# 3_mcu.net
KiCad netlist of a schematic drawn in Altium Designer
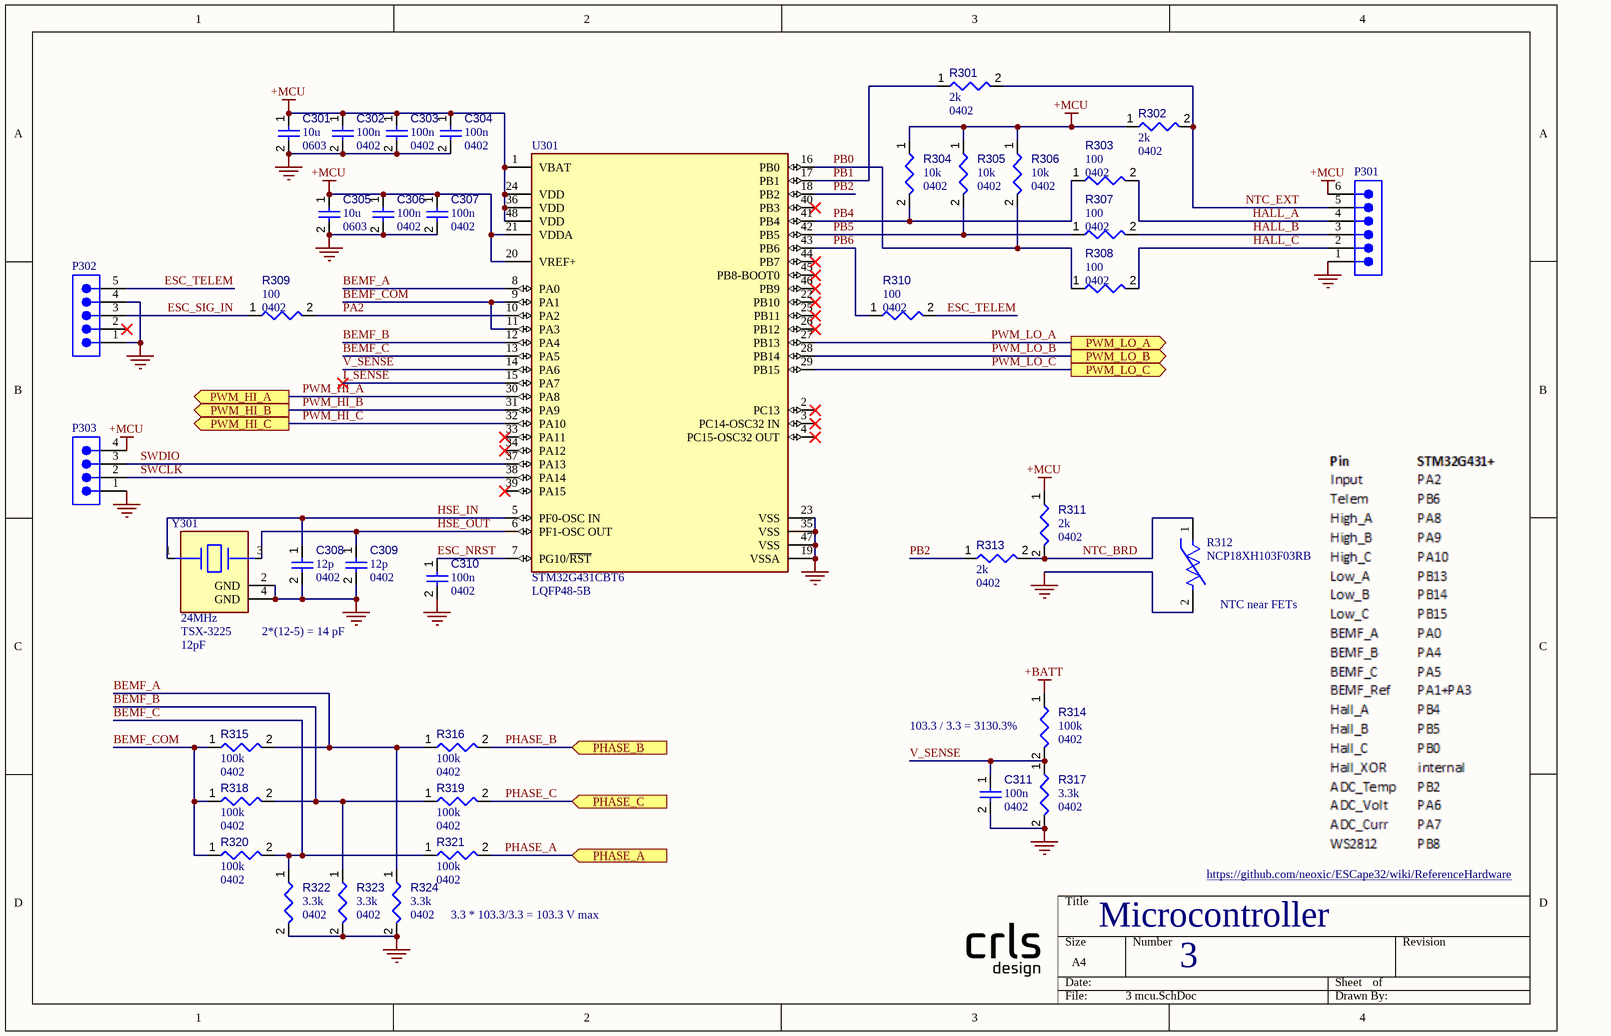
[diagram p0: 3 mcu.SchDoc]

(export (version "E")
  (design (tool "Eeschema 10.0.6"))
  (components
    (comp (ref "C301")
      (value "10u")
      (footprint "CAPC0603(1608)100_L")
      (description "Capacitor")
      (fields
        (field (name "CASE/PACKAGE") "0603")
        (field (name "TOLERANCE") "20%")
        (field (name "Comment") "Capacitors,ceramic,0603,20%,10u,25V")
      )
      (libsource (lib "UBC Uncrewed Aircraft Systems") (part "CAP-NP-2"))
    )
    (comp (ref "C302")
      (value "100n")
      (footprint "CAPC0402(1005)60_L")
      (description "Capacitor")
      (fields
        (field (name "CASE/PACKAGE") "0402")
        (field (name "TOLERANCE") "20%")
        (field (name "Comment") "Capacitors,ceramic,0402,20%,100n,16V")
      )
      (libsource (lib "UBC Uncrewed Aircraft Systems") (part "CAP-NP-2"))
    )
    (comp (ref "C303")
      (value "100n")
      (footprint "CAPC0402(1005)60_L")
      (description "Capacitor")
      (fields
        (field (name "CASE/PACKAGE") "0402")
        (field (name "TOLERANCE") "20%")
        (field (name "Comment") "Capacitors,ceramic,0402,20%,100n,16V")
      )
      (libsource (lib "UBC Uncrewed Aircraft Systems") (part "CAP-NP-2"))
    )
    (comp (ref "C304")
      (value "100n")
      (footprint "CAPC0402(1005)60_L")
      (description "Capacitor")
      (fields
        (field (name "CASE/PACKAGE") "0402")
        (field (name "TOLERANCE") "20%")
        (field (name "Comment") "Capacitors,ceramic,0402,20%,100n,16V")
      )
      (libsource (lib "UBC Uncrewed Aircraft Systems") (part "CAP-NP-2"))
    )
    (comp (ref "C305")
      (value "10u")
      (footprint "CAPC0603(1608)100_L")
      (description "Capacitor")
      (fields
        (field (name "CASE/PACKAGE") "0603")
        (field (name "TOLERANCE") "20%")
        (field (name "Comment") "Capacitors,ceramic,0603,20%,10u,25V")
      )
      (libsource (lib "UBC Uncrewed Aircraft Systems") (part "CAP-NP-2"))
    )
    (comp (ref "C306")
      (value "100n")
      (footprint "CAPC0402(1005)60_L")
      (description "Capacitor")
      (fields
        (field (name "CASE/PACKAGE") "0402")
        (field (name "TOLERANCE") "20%")
        (field (name "Comment") "Capacitors,ceramic,0402,20%,100n,16V")
      )
      (libsource (lib "UBC Uncrewed Aircraft Systems") (part "CAP-NP-2"))
    )
    (comp (ref "C307")
      (value "100n")
      (footprint "CAPC0402(1005)60_L")
      (description "Capacitor")
      (fields
        (field (name "CASE/PACKAGE") "0402")
        (field (name "TOLERANCE") "20%")
        (field (name "Comment") "Capacitors,ceramic,0402,20%,100n,16V")
      )
      (libsource (lib "UBC Uncrewed Aircraft Systems") (part "CAP-NP-2"))
    )
    (comp (ref "C308")
      (value "12p")
      (footprint "CAPC0402(1005)60_L")
      (description "Capacitor")
      (fields
        (field (name "CASE/PACKAGE") "0402")
        (field (name "TOLERANCE") "10%")
        (field (name "Comment") "Capacitors,ceramic,0402,10%,12p,50V")
      )
      (libsource (lib "UBC Uncrewed Aircraft Systems") (part "CAP-NP-2"))
    )
    (comp (ref "C309")
      (value "12p")
      (footprint "CAPC0402(1005)60_L")
      (description "Capacitor")
      (fields
        (field (name "CASE/PACKAGE") "0402")
        (field (name "TOLERANCE") "10%")
        (field (name "Comment") "Capacitors,ceramic,0402,10%,12p,50V")
      )
      (libsource (lib "UBC Uncrewed Aircraft Systems") (part "CAP-NP-2"))
    )
    (comp (ref "C310")
      (value "100n")
      (footprint "CAPC0402(1005)60_L")
      (description "Capacitor")
      (fields
        (field (name "CASE/PACKAGE") "0402")
        (field (name "TOLERANCE") "20%")
        (field (name "Comment") "Capacitors,ceramic,0402,20%,100n,16V")
      )
      (libsource (lib "UBC Uncrewed Aircraft Systems") (part "CAP-NP-2"))
    )
    (comp (ref "C311")
      (value "100n")
      (footprint "CAPC0402(1005)60_L")
      (description "Capacitor")
      (fields
        (field (name "CASE/PACKAGE") "0402")
        (field (name "TOLERANCE") "20%")
        (field (name "Comment") "Capacitors,ceramic,0402,20%,100n,16V")
      )
      (libsource (lib "UBC Uncrewed Aircraft Systems") (part "CAP-NP-2"))
    )
    (comp (ref "P301")
      (value "61300611121")
      (footprint "61300611121")
      (libsource (lib "Altium Content Vault") (part "Header_Male_1R_06P"))
    )
    (comp (ref "P302")
      (value "61300511121")
      (footprint "61300511121")
      (libsource (lib "Altium Content Vault") (part "Header_Male_1R_05P"))
    )
    (comp (ref "P303")
      (value "61300411121")
      (footprint "61300411121")
      (libsource (lib "Altium Content Vault") (part "Header_Male_1R_04P"))
    )
    (comp (ref "R301")
      (value "2k")
      (footprint "RESC0402(1005)_L")
      (description "Resistor")
      (fields
        (field (name "CASE/PACKAGE") "0402")
        (field (name "TOLERANCE") "1%")
        (field (name "Comment") "Resistors,0402,1%,2k")
      )
      (libsource (lib "UBC Uncrewed Aircraft Systems") (part "RES-2"))
    )
    (comp (ref "R302")
      (value "2k")
      (footprint "RESC0402(1005)_L")
      (description "Resistor")
      (fields
        (field (name "CASE/PACKAGE") "0402")
        (field (name "TOLERANCE") "1%")
        (field (name "Comment") "Resistors,0402,1%,2k")
      )
      (libsource (lib "UBC Uncrewed Aircraft Systems") (part "RES-2"))
    )
    (comp (ref "R303")
      (value "100")
      (footprint "RESC0402(1005)_L")
      (description "Resistor")
      (fields
        (field (name "CASE/PACKAGE") "0402")
        (field (name "TOLERANCE") "1%")
        (field (name "Comment") "Resistors,0402,1%,100")
      )
      (libsource (lib "UBC Uncrewed Aircraft Systems") (part "RES-2"))
    )
    (comp (ref "R304")
      (value "10k")
      (footprint "RESC0402(1005)_L")
      (description "Resistor")
      (fields
        (field (name "CASE/PACKAGE") "0402")
        (field (name "TOLERANCE") "1%")
        (field (name "Comment") "Resistors,0402,1%,10k")
      )
      (libsource (lib "UBC Uncrewed Aircraft Systems") (part "RES-2"))
    )
    (comp (ref "R305")
      (value "10k")
      (footprint "RESC0402(1005)_L")
      (description "Resistor")
      (fields
        (field (name "CASE/PACKAGE") "0402")
        (field (name "TOLERANCE") "1%")
        (field (name "Comment") "Resistors,0402,1%,10k")
      )
      (libsource (lib "UBC Uncrewed Aircraft Systems") (part "RES-2"))
    )
    (comp (ref "R306")
      (value "10k")
      (footprint "RESC0402(1005)_L")
      (description "Resistor")
      (fields
        (field (name "CASE/PACKAGE") "0402")
        (field (name "TOLERANCE") "1%")
        (field (name "Comment") "Resistors,0402,1%,10k")
      )
      (libsource (lib "UBC Uncrewed Aircraft Systems") (part "RES-2"))
    )
    (comp (ref "R307")
      (value "100")
      (footprint "RESC0402(1005)_L")
      (description "Resistor")
      (fields
        (field (name "CASE/PACKAGE") "0402")
        (field (name "TOLERANCE") "1%")
        (field (name "Comment") "Resistors,0402,1%,100")
      )
      (libsource (lib "UBC Uncrewed Aircraft Systems") (part "RES-2"))
    )
    (comp (ref "R308")
      (value "100")
      (footprint "RESC0402(1005)_L")
      (description "Resistor")
      (fields
        (field (name "CASE/PACKAGE") "0402")
        (field (name "TOLERANCE") "1%")
        (field (name "Comment") "Resistors,0402,1%,100")
      )
      (libsource (lib "UBC Uncrewed Aircraft Systems") (part "RES-2"))
    )
    (comp (ref "R309")
      (value "100")
      (footprint "RESC0402(1005)_L")
      (description "Resistor")
      (fields
        (field (name "CASE/PACKAGE") "0402")
        (field (name "TOLERANCE") "1%")
        (field (name "Comment") "Resistors,0402,1%,100")
      )
      (libsource (lib "UBC Uncrewed Aircraft Systems") (part "RES-2"))
    )
    (comp (ref "R310")
      (value "100")
      (footprint "RESC0402(1005)_L")
      (description "Resistor")
      (fields
        (field (name "CASE/PACKAGE") "0402")
        (field (name "TOLERANCE") "1%")
        (field (name "Comment") "Resistors,0402,1%,100")
      )
      (libsource (lib "UBC Uncrewed Aircraft Systems") (part "RES-2"))
    )
    (comp (ref "R311")
      (value "2k")
      (footprint "RESC0402(1005)_L")
      (description "Resistor")
      (fields
        (field (name "CASE/PACKAGE") "0402")
        (field (name "TOLERANCE") "1%")
        (field (name "Comment") "Resistors,0402,1%,2k")
      )
      (libsource (lib "UBC Uncrewed Aircraft Systems") (part "RES-2"))
    )
    (comp (ref "R312")
      (value "NCP18XH103F03RB")
      (footprint "FP-NCP18-0_15-MFG")
      (description "NTC Thermistor for Temperature Sensor, 0603, 10kΩ, 1%, 0.1mA, 5V")
      (fields (field (name "TOLERANCE") "1%"))
      (libsource (lib "Altium Content Vault") (part "3b148a6ebabc5fb4d708a66c052d352"))
    )
    (comp (ref "R313")
      (value "2k")
      (footprint "RESC0402(1005)_L")
      (description "Resistor")
      (fields
        (field (name "CASE/PACKAGE") "0402")
        (field (name "TOLERANCE") "1%")
        (field (name "Comment") "Resistors,0402,1%,2k")
      )
      (libsource (lib "UBC Uncrewed Aircraft Systems") (part "RES-2"))
    )
    (comp (ref "R314")
      (value "100k")
      (footprint "RESC0402(1005)_L")
      (description "Resistor")
      (fields
        (field (name "CASE/PACKAGE") "0402")
        (field (name "TOLERANCE") "1%")
        (field (name "Comment") "Resistors,0402,1%,100k")
      )
      (libsource (lib "UBC Uncrewed Aircraft Systems") (part "RES-2"))
    )
    (comp (ref "R315")
      (value "100k")
      (footprint "RESC0402(1005)_L")
      (description "Resistor")
      (fields
        (field (name "CASE/PACKAGE") "0402")
        (field (name "TOLERANCE") "1%")
        (field (name "Comment") "Resistors,0402,1%,100k")
      )
      (libsource (lib "UBC Uncrewed Aircraft Systems") (part "RES-2"))
    )
    (comp (ref "R316")
      (value "100k")
      (footprint "RESC0402(1005)_L")
      (description "Resistor")
      (fields
        (field (name "CASE/PACKAGE") "0402")
        (field (name "TOLERANCE") "1%")
        (field (name "Comment") "Resistors,0402,1%,100k")
      )
      (libsource (lib "UBC Uncrewed Aircraft Systems") (part "RES-2"))
    )
    (comp (ref "R317")
      (value "3.3k")
      (footprint "RESC0402(1005)_L")
      (description "Resistor")
      (fields
        (field (name "CASE/PACKAGE") "0402")
        (field (name "TOLERANCE") "1%")
        (field (name "Comment") "Resistors,0402,1%,3.3k")
      )
      (libsource (lib "UBC Uncrewed Aircraft Systems") (part "RES-2"))
    )
    (comp (ref "R318")
      (value "100k")
      (footprint "RESC0402(1005)_L")
      (description "Resistor")
      (fields
        (field (name "CASE/PACKAGE") "0402")
        (field (name "TOLERANCE") "1%")
        (field (name "Comment") "Resistors,0402,1%,100k")
      )
      (libsource (lib "UBC Uncrewed Aircraft Systems") (part "RES-2"))
    )
    (comp (ref "R319")
      (value "100k")
      (footprint "RESC0402(1005)_L")
      (description "Resistor")
      (fields
        (field (name "CASE/PACKAGE") "0402")
        (field (name "TOLERANCE") "1%")
        (field (name "Comment") "Resistors,0402,1%,100k")
      )
      (libsource (lib "UBC Uncrewed Aircraft Systems") (part "RES-2"))
    )
    (comp (ref "R320")
      (value "100k")
      (footprint "RESC0402(1005)_L")
      (description "Resistor")
      (fields
        (field (name "CASE/PACKAGE") "0402")
        (field (name "TOLERANCE") "1%")
        (field (name "Comment") "Resistors,0402,1%,100k")
      )
      (libsource (lib "UBC Uncrewed Aircraft Systems") (part "RES-2"))
    )
    (comp (ref "R321")
      (value "100k")
      (footprint "RESC0402(1005)_L")
      (description "Resistor")
      (fields
        (field (name "CASE/PACKAGE") "0402")
        (field (name "TOLERANCE") "1%")
        (field (name "Comment") "Resistors,0402,1%,100k")
      )
      (libsource (lib "UBC Uncrewed Aircraft Systems") (part "RES-2"))
    )
    (comp (ref "R322")
      (value "3.3k")
      (footprint "RESC0402(1005)_L")
      (description "Resistor")
      (fields
        (field (name "CASE/PACKAGE") "0402")
        (field (name "TOLERANCE") "1%")
        (field (name "Comment") "Resistors,0402,1%,3.3k")
      )
      (libsource (lib "UBC Uncrewed Aircraft Systems") (part "RES-2"))
    )
    (comp (ref "R323")
      (value "3.3k")
      (footprint "RESC0402(1005)_L")
      (description "Resistor")
      (fields
        (field (name "CASE/PACKAGE") "0402")
        (field (name "TOLERANCE") "1%")
        (field (name "Comment") "Resistors,0402,1%,3.3k")
      )
      (libsource (lib "UBC Uncrewed Aircraft Systems") (part "RES-2"))
    )
    (comp (ref "R324")
      (value "3.3k")
      (footprint "RESC0402(1005)_L")
      (description "Resistor")
      (fields
        (field (name "CASE/PACKAGE") "0402")
        (field (name "TOLERANCE") "1%")
        (field (name "Comment") "Resistors,0402,1%,3.3k")
      )
      (libsource (lib "UBC Uncrewed Aircraft Systems") (part "RES-2"))
    )
    (comp (ref "U301")
      (value "STM32G431CBT6")
      (footprint "FP-LQFP48-5B-MFG")
      (description "MAINSTREAM ARM CORTEX-M4+ MCU 17")
      (fields
        (field (name "MANUFACTURER") "STMicroelectronics")
        (field (name "PACKAGE") "LQFP48-5B")
        (field (name "OCTOPART") "https://octopart.com/stm32g431cbt6-stmicroelectronics-98835224")
      )
      (libsource (lib "Altium Content Vault") (part "08b09c1d51ec08ade740842f2b8671b"))
    )
    (comp (ref "Y301")
      (value "TSX-3225 24.0000MF20G-AC3")
      (footprint "FP-TSX-3225-MFG")
      (description "CRYSTAL 24.0000MHZ 9PF SMD")
      (fields
        (field (name "FREQUENCY") "24MHz")
        (field (name "TOLERANCE") "10ppm")
        (field (name "SERIES") "TSX-3225")
      )
      (libsource (lib "Altium Content Vault") (part "862d5228ea4a4c8f16e8fb874e464c7"))
    )
  )
  (nets
    (net (code "1") (name "+BATT") (class "Default")
      (node (ref "R314") (pin "1") (pinfunction "1_1") (pintype "passive"))
    )
    (net (code "2") (name "+MCU") (class "Default")
      (node (ref "C301") (pin "1") (pinfunction "1_1") (pintype "passive"))
      (node (ref "C302") (pin "1") (pinfunction "1_1") (pintype "passive"))
      (node (ref "C303") (pin "1") (pinfunction "1_1") (pintype "passive"))
      (node (ref "C304") (pin "1") (pinfunction "1_1") (pintype "passive"))
      (node (ref "C305") (pin "1") (pinfunction "1_1") (pintype "passive"))
      (node (ref "C306") (pin "1") (pinfunction "1_1") (pintype "passive"))
      (node (ref "C307") (pin "1") (pinfunction "1_1") (pintype "passive"))
      (node (ref "P301") (pin "6") (pinfunction "6_6") (pintype "passive"))
      (node (ref "P303") (pin "4") (pinfunction "4_4") (pintype "passive"))
      (node (ref "R302") (pin "1") (pinfunction "1_1") (pintype "passive"))
      (node (ref "R304") (pin "1") (pinfunction "1_1") (pintype "passive"))
      (node (ref "R305") (pin "1") (pinfunction "1_1") (pintype "passive"))
      (node (ref "R306") (pin "1") (pinfunction "1_1") (pintype "passive"))
      (node (ref "R311") (pin "1") (pinfunction "1_1") (pintype "passive"))
      (node (ref "U301") (pin "1") (pinfunction "VBAT_1") (pintype "power_in"))
      (node (ref "U301") (pin "20") (pinfunction "VREF+_20") (pintype "power_in"))
      (node (ref "U301") (pin "21") (pinfunction "VDDA_21") (pintype "power_in"))
      (node (ref "U301") (pin "24") (pinfunction "VDD_24") (pintype "power_in"))
      (node (ref "U301") (pin "36") (pinfunction "VDD_36") (pintype "power_in"))
      (node (ref "U301") (pin "48") (pinfunction "VDD_48") (pintype "power_in"))
    )
    (net (code "3") (name "/BEMF_A") (class "Default")
      (node (ref "R315") (pin "2") (pinfunction "2_2") (pintype "passive"))
      (node (ref "R316") (pin "1") (pinfunction "1_1") (pintype "passive"))
      (node (ref "R324") (pin "1") (pinfunction "1_1") (pintype "passive"))
      (node (ref "U301") (pin "8") (pinfunction "PA0_8") (pintype "bidirectional"))
    )
    (net (code "4") (name "/BEMF_B") (class "Default")
      (node (ref "R318") (pin "2") (pinfunction "2_2") (pintype "passive"))
      (node (ref "R319") (pin "1") (pinfunction "1_1") (pintype "passive"))
      (node (ref "R323") (pin "1") (pinfunction "1_1") (pintype "passive"))
      (node (ref "U301") (pin "12") (pinfunction "PA4_12") (pintype "bidirectional"))
    )
    (net (code "5") (name "/BEMF_C") (class "Default")
      (node (ref "R320") (pin "2") (pinfunction "2_2") (pintype "passive"))
      (node (ref "R321") (pin "1") (pinfunction "1_1") (pintype "passive"))
      (node (ref "R322") (pin "1") (pinfunction "1_1") (pintype "passive"))
      (node (ref "U301") (pin "13") (pinfunction "PA5_13") (pintype "bidirectional"))
    )
    (net (code "6") (name "/BEMF_COM") (class "Default")
      (node (ref "R315") (pin "1") (pinfunction "1_1") (pintype "passive"))
      (node (ref "R318") (pin "1") (pinfunction "1_1") (pintype "passive"))
      (node (ref "R320") (pin "1") (pinfunction "1_1") (pintype "passive"))
      (node (ref "U301") (pin "11") (pinfunction "PA3_11") (pintype "bidirectional"))
      (node (ref "U301") (pin "9") (pinfunction "PA1_9") (pintype "bidirectional"))
    )
    (net (code "7") (name "/ESC_NRST") (class "Default")
      (node (ref "C310") (pin "1") (pinfunction "1_1") (pintype "passive"))
      (node (ref "U301") (pin "7") (pinfunction "PG10/~{RST}_7") (pintype "bidirectional"))
    )
    (net (code "8") (name "/ESC_SIG_IN") (class "Default")
      (node (ref "P302") (pin "3") (pinfunction "3_3") (pintype "passive"))
      (node (ref "R309") (pin "1") (pinfunction "1_1") (pintype "passive"))
    )
    (net (code "9") (name "/ESC_TELEM") (class "Default")
      (node (ref "P302") (pin "5") (pinfunction "5_5") (pintype "passive"))
      (node (ref "R310") (pin "2") (pinfunction "2_2") (pintype "passive"))
    )
    (net (code "10") (name "/HALL_A") (class "Default")
      (node (ref "P301") (pin "4") (pinfunction "4_4") (pintype "passive"))
      (node (ref "R303") (pin "2") (pinfunction "2_2") (pintype "passive"))
    )
    (net (code "11") (name "/HALL_B") (class "Default")
      (node (ref "P301") (pin "3") (pinfunction "3_3") (pintype "passive"))
      (node (ref "R307") (pin "2") (pinfunction "2_2") (pintype "passive"))
    )
    (net (code "12") (name "/HALL_C") (class "Default")
      (node (ref "P301") (pin "2") (pinfunction "2_2") (pintype "passive"))
      (node (ref "R308") (pin "2") (pinfunction "2_2") (pintype "passive"))
    )
    (net (code "13") (name "/HSE_IN") (class "Default")
      (node (ref "C308") (pin "1") (pinfunction "1_1") (pintype "passive"))
      (node (ref "U301") (pin "5") (pinfunction "PF0-OSC_IN_5") (pintype "bidirectional"))
      (node (ref "Y301") (pin "1") (pinfunction "1_1") (pintype "passive"))
    )
    (net (code "14") (name "/HSE_OUT") (class "Default")
      (node (ref "C309") (pin "1") (pinfunction "1_1") (pintype "passive"))
      (node (ref "U301") (pin "6") (pinfunction "PF1-OSC_OUT_6") (pintype "bidirectional"))
      (node (ref "Y301") (pin "3") (pinfunction "3_3") (pintype "passive"))
    )
    (net (code "15") (name "/I_SENSE") (class "Default")
      (node (ref "U301") (pin "15") (pinfunction "PA7_15") (pintype "bidirectional+no_connect"))
    )
    (net (code "16") (name "/NTC_BRD") (class "Default")
      (node (ref "R311") (pin "2") (pinfunction "2_2") (pintype "passive"))
      (node (ref "R312") (pin "1") (pinfunction "1_1") (pintype "passive"))
      (node (ref "R313") (pin "2") (pinfunction "2_2") (pintype "passive"))
    )
    (net (code "17") (name "/NTC_EXT") (class "Default")
      (node (ref "P301") (pin "5") (pinfunction "5_5") (pintype "passive"))
      (node (ref "R301") (pin "2") (pinfunction "2_2") (pintype "passive"))
      (node (ref "R302") (pin "2") (pinfunction "2_2") (pintype "passive"))
    )
    (net (code "18") (name "/PA2") (class "Default")
      (node (ref "R309") (pin "2") (pinfunction "2_2") (pintype "passive"))
      (node (ref "U301") (pin "10") (pinfunction "PA2_10") (pintype "bidirectional"))
    )
    (net (code "19") (name "/PB0") (class "Default")
      (node (ref "R306") (pin "2") (pinfunction "2_2") (pintype "passive"))
      (node (ref "R308") (pin "1") (pinfunction "1_1") (pintype "passive"))
      (node (ref "U301") (pin "16") (pinfunction "PB0_16") (pintype "bidirectional"))
    )
    (net (code "20") (name "/PB1") (class "Default")
      (node (ref "R301") (pin "1") (pinfunction "1_1") (pintype "passive"))
      (node (ref "U301") (pin "17") (pinfunction "PB1_17") (pintype "bidirectional"))
    )
    (net (code "21") (name "/PB2") (class "Default")
      (node (ref "R313") (pin "1") (pinfunction "1_1") (pintype "passive"))
      (node (ref "U301") (pin "18") (pinfunction "PB2_18") (pintype "bidirectional"))
    )
    (net (code "22") (name "/PB4") (class "Default")
      (node (ref "R303") (pin "1") (pinfunction "1_1") (pintype "passive"))
      (node (ref "R304") (pin "2") (pinfunction "2_2") (pintype "passive"))
      (node (ref "U301") (pin "41") (pinfunction "PB4_41") (pintype "bidirectional"))
    )
    (net (code "23") (name "/PB5") (class "Default")
      (node (ref "R305") (pin "2") (pinfunction "2_2") (pintype "passive"))
      (node (ref "R307") (pin "1") (pinfunction "1_1") (pintype "passive"))
      (node (ref "U301") (pin "42") (pinfunction "PB5_42") (pintype "bidirectional"))
    )
    (net (code "24") (name "/PB6") (class "Default")
      (node (ref "R310") (pin "1") (pinfunction "1_1") (pintype "passive"))
      (node (ref "U301") (pin "43") (pinfunction "PB6_43") (pintype "bidirectional"))
    )
    (net (code "25") (name "/PHASE_A") (class "Default")
      (node (ref "R321") (pin "2") (pinfunction "2_2") (pintype "passive"))
    )
    (net (code "26") (name "/PHASE_B") (class "Default")
      (node (ref "R316") (pin "2") (pinfunction "2_2") (pintype "passive"))
    )
    (net (code "27") (name "/PHASE_C") (class "Default")
      (node (ref "R319") (pin "2") (pinfunction "2_2") (pintype "passive"))
    )
    (net (code "28") (name "/PWM_HI_A") (class "Default")
      (node (ref "U301") (pin "30") (pinfunction "PA8_30") (pintype "bidirectional"))
    )
    (net (code "29") (name "/PWM_HI_B") (class "Default")
      (node (ref "U301") (pin "31") (pinfunction "PA9_31") (pintype "bidirectional"))
    )
    (net (code "30") (name "/PWM_HI_C") (class "Default")
      (node (ref "U301") (pin "32") (pinfunction "PA10_32") (pintype "bidirectional"))
    )
    (net (code "31") (name "/PWM_LO_A") (class "Default")
      (node (ref "U301") (pin "27") (pinfunction "PB13_27") (pintype "bidirectional"))
    )
    (net (code "32") (name "/PWM_LO_B") (class "Default")
      (node (ref "U301") (pin "28") (pinfunction "PB14_28") (pintype "bidirectional"))
    )
    (net (code "33") (name "/PWM_LO_C") (class "Default")
      (node (ref "U301") (pin "29") (pinfunction "PB15_29") (pintype "bidirectional"))
    )
    (net (code "34") (name "/SWCLK") (class "Default")
      (node (ref "P303") (pin "2") (pinfunction "2_2") (pintype "passive"))
      (node (ref "U301") (pin "38") (pinfunction "PA14_38") (pintype "bidirectional"))
    )
    (net (code "35") (name "/SWDIO") (class "Default")
      (node (ref "P303") (pin "3") (pinfunction "3_3") (pintype "passive"))
      (node (ref "U301") (pin "37") (pinfunction "PA13_37") (pintype "bidirectional"))
    )
    (net (code "36") (name "/V_SENSE") (class "Default")
      (node (ref "C311") (pin "1") (pinfunction "1_1") (pintype "passive"))
      (node (ref "R314") (pin "2") (pinfunction "2_2") (pintype "passive"))
      (node (ref "R317") (pin "1") (pinfunction "1_1") (pintype "passive"))
      (node (ref "U301") (pin "14") (pinfunction "PA6_14") (pintype "bidirectional"))
    )
    (net (code "37") (name "GND") (class "Default")
      (node (ref "C301") (pin "2") (pinfunction "2_2") (pintype "passive"))
      (node (ref "C302") (pin "2") (pinfunction "2_2") (pintype "passive"))
      (node (ref "C303") (pin "2") (pinfunction "2_2") (pintype "passive"))
      (node (ref "C304") (pin "2") (pinfunction "2_2") (pintype "passive"))
      (node (ref "C305") (pin "2") (pinfunction "2_2") (pintype "passive"))
      (node (ref "C306") (pin "2") (pinfunction "2_2") (pintype "passive"))
      (node (ref "C307") (pin "2") (pinfunction "2_2") (pintype "passive"))
      (node (ref "C308") (pin "2") (pinfunction "2_2") (pintype "passive"))
      (node (ref "C309") (pin "2") (pinfunction "2_2") (pintype "passive"))
      (node (ref "C310") (pin "2") (pinfunction "2_2") (pintype "passive"))
      (node (ref "C311") (pin "2") (pinfunction "2_2") (pintype "passive"))
      (node (ref "P301") (pin "1") (pinfunction "1_1") (pintype "passive"))
      (node (ref "P302") (pin "1") (pinfunction "1_1") (pintype "passive"))
      (node (ref "P302") (pin "4") (pinfunction "4_4") (pintype "passive"))
      (node (ref "P303") (pin "1") (pinfunction "1_1") (pintype "passive"))
      (node (ref "R312") (pin "2") (pinfunction "2_2") (pintype "passive"))
      (node (ref "R317") (pin "2") (pinfunction "2_2") (pintype "passive"))
      (node (ref "R322") (pin "2") (pinfunction "2_2") (pintype "passive"))
      (node (ref "R323") (pin "2") (pinfunction "2_2") (pintype "passive"))
      (node (ref "R324") (pin "2") (pinfunction "2_2") (pintype "passive"))
      (node (ref "U301") (pin "19") (pinfunction "VSSA_19") (pintype "power_in"))
      (node (ref "U301") (pin "23") (pinfunction "VSS_23") (pintype "power_in"))
      (node (ref "U301") (pin "35") (pinfunction "VSS_35") (pintype "power_in"))
      (node (ref "U301") (pin "47") (pinfunction "VSS_47") (pintype "power_in"))
      (node (ref "Y301") (pin "2") (pinfunction "GND_2") (pintype "power_in"))
      (node (ref "Y301") (pin "4") (pinfunction "GND_4") (pintype "power_in"))
    )
    (net (code "38") (name "unconnected-(P302-Pad2)") (class "Default")
      (node (ref "P302") (pin "2") (pinfunction "2_2") (pintype "passive+no_connect"))
    )
    (net (code "39") (name "unconnected-(U301-PA11-Pad33)") (class "Default")
      (node (ref "U301") (pin "33") (pinfunction "PA11_33") (pintype "bidirectional+no_connect"))
    )
    (net (code "40") (name "unconnected-(U301-PA12-Pad34)") (class "Default")
      (node (ref "U301") (pin "34") (pinfunction "PA12_34") (pintype "bidirectional+no_connect"))
    )
    (net (code "41") (name "unconnected-(U301-PA15-Pad39)") (class "Default")
      (node (ref "U301") (pin "39") (pinfunction "PA15_39") (pintype "bidirectional+no_connect"))
    )
    (net (code "42") (name "unconnected-(U301-PB3-Pad40)") (class "Default")
      (node (ref "U301") (pin "40") (pinfunction "PB3_40") (pintype "bidirectional+no_connect"))
    )
    (net (code "43") (name "unconnected-(U301-PB7-Pad44)") (class "Default")
      (node (ref "U301") (pin "44") (pinfunction "PB7_44") (pintype "bidirectional+no_connect"))
    )
    (net (code "44") (name "unconnected-(U301-PB8-BOOT0-Pad45)") (class "Default")
      (node (ref "U301") (pin "45") (pinfunction "PB8-BOOT0_45") (pintype "bidirectional+no_connect"))
    )
    (net (code "45") (name "unconnected-(U301-PB9-Pad46)") (class "Default")
      (node (ref "U301") (pin "46") (pinfunction "PB9_46") (pintype "bidirectional+no_connect"))
    )
    (net (code "46") (name "unconnected-(U301-PB10-Pad22)") (class "Default")
      (node (ref "U301") (pin "22") (pinfunction "PB10_22") (pintype "bidirectional+no_connect"))
    )
    (net (code "47") (name "unconnected-(U301-PB11-Pad25)") (class "Default")
      (node (ref "U301") (pin "25") (pinfunction "PB11_25") (pintype "bidirectional+no_connect"))
    )
    (net (code "48") (name "unconnected-(U301-PB12-Pad26)") (class "Default")
      (node (ref "U301") (pin "26") (pinfunction "PB12_26") (pintype "bidirectional+no_connect"))
    )
    (net (code "49") (name "unconnected-(U301-PC13-Pad2)") (class "Default")
      (node (ref "U301") (pin "2") (pinfunction "PC13_2") (pintype "bidirectional+no_connect"))
    )
    (net (code "50") (name "unconnected-(U301-PC14-OSC32_IN-Pad3)") (class "Default")
      (node (ref "U301") (pin "3") (pinfunction "PC14-OSC32_IN_3") (pintype "bidirectional+no_connect"))
    )
    (net (code "51") (name "unconnected-(U301-PC15-OSC32_OUT-Pad4)") (class "Default")
      (node (ref "U301") (pin "4") (pinfunction "PC15-OSC32_OUT_4") (pintype "bidirectional+no_connect"))
    )
  )
)
